# TemperatureMonitor-NTC.net
KiCad netlist of a schematic drawn in EAGLE
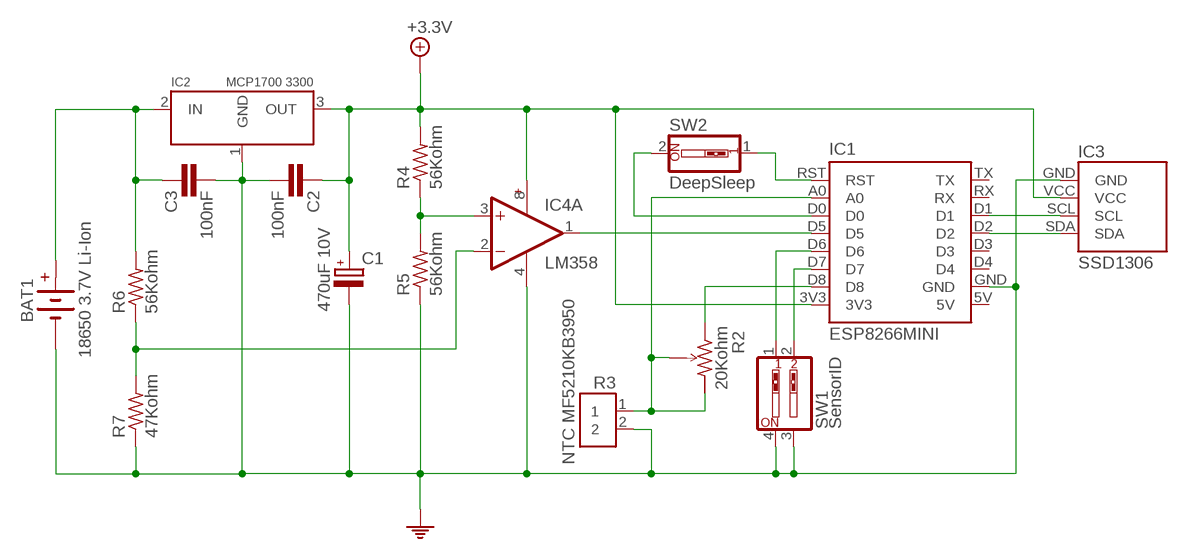
[diagram p0: schematic, sheet 1]

(export (version "E")
  (design (tool "Eeschema 10.0.6"))
  (components
    (comp (ref "BAT1")
      (value "18650 3.7V Li-Ion")
      (footprint "eagle-import:SIL2")
      (libsource (lib "eagle-import") (part "BATTERYSIL2"))
    )
    (comp (ref "C1")
      (value "470uF 10V")
      (footprint "eagle-import:CAPACITOR-5MM")
      (libsource (lib "eagle-import") (part "CAPACITOR_EL5MM"))
    )
    (comp (ref "C2")
      (value "100nF")
      (footprint "eagle-import:CAPACITOR-5MM")
      (libsource (lib "eagle-import") (part "CAPACITOR5MM"))
    )
    (comp (ref "C3")
      (value "100nF")
      (footprint "eagle-import:CAPACITOR-5MM")
      (libsource (lib "eagle-import") (part "CAPACITOR5MM"))
    )
    (comp (ref "IC1")
      (value "ESP8266MINI")
      (footprint "eagle-import:ESP8266MINI")
      (libsource (lib "eagle-import") (part "ESP8266MINI"))
    )
    (comp (ref "IC2")
      (value "MCP1700 3300")
      (footprint "eagle-import:TO92")
      (libsource (lib "eagle-import") (part "MCP1700"))
    )
    (comp (ref "IC3")
      (value "SSD1306")
      (footprint "eagle-import:SSD1306")
      (libsource (lib "eagle-import") (part "SSD1306"))
    )
    (comp (ref "IC4")
      (value "LM358")
      (footprint "eagle-import:DIL8")
      (fields (field (name "SPICEPREFIX") "J"))
      (libsource (lib "eagle-import") (part "LM358"))
    )
    (comp (ref "R2")
      (value "20Kohm")
      (footprint "eagle-import:TRIMMER-A")
      (libsource (lib "eagle-import") (part "TRIMMERA"))
    )
    (comp (ref "R3")
      (value "NTC MF5210KB3950")
      (footprint "eagle-import:JST2")
      (libsource (lib "eagle-import") (part "SIL2JST2"))
    )
    (comp (ref "R4")
      (value "56Kohm")
      (footprint "eagle-import:RESISTOR-0.25W")
      (libsource (lib "eagle-import") (part "RESISTOR0.25W"))
    )
    (comp (ref "R5")
      (value "56Kohm")
      (footprint "eagle-import:RESISTOR-0.25W")
      (libsource (lib "eagle-import") (part "RESISTOR0.25W"))
    )
    (comp (ref "R6")
      (value "56Kohm")
      (footprint "eagle-import:RESISTOR-0.25W")
      (libsource (lib "eagle-import") (part "RESISTOR0.25W"))
    )
    (comp (ref "R7")
      (value "47Kohm")
      (footprint "eagle-import:RESISTOR-0.25W")
      (libsource (lib "eagle-import") (part "RESISTOR0.25W"))
    )
    (comp (ref "SW1")
      (value "SensorID")
      (footprint "eagle-import:DIL4")
      (libsource (lib "eagle-import") (part "DIP-SWITCH-2"))
    )
    (comp (ref "SW2")
      (value "DeepSleep")
      (footprint "eagle-import:DIL2")
      (libsource (lib "eagle-import") (part "DIP-SWITCH-1"))
    )
  )
  (nets
    (net (code "1") (name "+3.3V") (class "Default")
      (node (ref "C1") (pin "1") (pinfunction "1_1") (pintype "passive"))
      (node (ref "C2") (pin "1") (pinfunction "1_1") (pintype "passive"))
      (node (ref "IC1") (pin "3V3") (pinfunction "3V3_3V3") (pintype "power_in"))
      (node (ref "IC2") (pin "3") (pinfunction "OUT_3") (pintype "output"))
      (node (ref "IC3") (pin "VCC") (pinfunction "VCC_VCC") (pintype "power_in"))
      (node (ref "IC4") (pin "8") (pinfunction "V+_8") (pintype "power_in"))
      (node (ref "R4") (pin "2") (pinfunction "2_2") (pintype "passive"))
    )
    (net (code "2") (name "/5V") (class "Default")
      (node (ref "IC1") (pin "5V") (pinfunction "5V_5V") (pintype "power_in"))
    )
    (net (code "3") (name "GND") (class "Default")
      (node (ref "BAT1") (pin "2") (pinfunction "-_2") (pintype "passive"))
      (node (ref "C1") (pin "2") (pinfunction "2_2") (pintype "passive"))
      (node (ref "C2") (pin "2") (pinfunction "2_2") (pintype "passive"))
      (node (ref "C3") (pin "1") (pinfunction "1_1") (pintype "passive"))
      (node (ref "IC1") (pin "GND") (pinfunction "GND_GND") (pintype "power_in"))
      (node (ref "IC2") (pin "1") (pinfunction "GND_1") (pintype "power_in"))
      (node (ref "IC3") (pin "GND") (pinfunction "GND_GND") (pintype "power_in"))
      (node (ref "IC4") (pin "4") (pinfunction "V-_4") (pintype "power_in"))
      (node (ref "R3") (pin "2") (pinfunction "2_2") (pintype "bidirectional"))
      (node (ref "R5") (pin "1") (pinfunction "1_1") (pintype "passive"))
      (node (ref "R7") (pin "1") (pinfunction "1_1") (pintype "passive"))
      (node (ref "SW1") (pin "3") (pinfunction "3_3") (pintype "passive"))
      (node (ref "SW1") (pin "4") (pinfunction "4_4") (pintype "passive"))
    )
    (net (code "4") (name "Net-(BAT1-+)") (class "Default")
      (node (ref "BAT1") (pin "1") (pinfunction "+_1") (pintype "passive"))
      (node (ref "C3") (pin "2") (pinfunction "2_2") (pintype "passive"))
      (node (ref "IC2") (pin "2") (pinfunction "IN_2") (pintype "input"))
      (node (ref "R6") (pin "2") (pinfunction "2_2") (pintype "passive"))
    )
    (net (code "5") (name "Net-(IC1-PadA0)") (class "Default")
      (node (ref "IC1") (pin "A0") (pinfunction "A0_A0") (pintype "bidirectional"))
      (node (ref "R2") (pin "B") (pinfunction "B_B") (pintype "passive"))
      (node (ref "R2") (pin "C") (pinfunction "C_C") (pintype "passive"))
      (node (ref "R3") (pin "1") (pinfunction "1_1") (pintype "bidirectional"))
    )
    (net (code "6") (name "Net-(IC1-PadD0)") (class "Default")
      (node (ref "IC1") (pin "D0") (pinfunction "D0_D0") (pintype "bidirectional"))
      (node (ref "SW2") (pin "2") (pinfunction "2_2") (pintype "passive"))
    )
    (net (code "7") (name "Net-(IC1-PadD1)") (class "Default")
      (node (ref "IC1") (pin "D1") (pinfunction "D1_D1") (pintype "bidirectional"))
      (node (ref "IC3") (pin "SCL") (pinfunction "SCL_SCL") (pintype "bidirectional"))
    )
    (net (code "8") (name "Net-(IC1-PadD2)") (class "Default")
      (node (ref "IC1") (pin "D2") (pinfunction "D2_D2") (pintype "bidirectional"))
      (node (ref "IC3") (pin "SDA") (pinfunction "SDA_SDA") (pintype "bidirectional"))
    )
    (net (code "9") (name "Net-(IC1-PadD6)") (class "Default")
      (node (ref "IC1") (pin "D6") (pinfunction "D6_D6") (pintype "bidirectional"))
      (node (ref "SW1") (pin "1") (pinfunction "1_1") (pintype "passive"))
    )
    (net (code "10") (name "Net-(IC1-PadD7)") (class "Default")
      (node (ref "IC1") (pin "D7") (pinfunction "D7_D7") (pintype "bidirectional"))
      (node (ref "SW1") (pin "2") (pinfunction "2_2") (pintype "passive"))
    )
    (net (code "11") (name "Net-(IC1-PadD8)") (class "Default")
      (node (ref "IC1") (pin "D8") (pinfunction "D8_D8") (pintype "bidirectional"))
      (node (ref "R2") (pin "A") (pinfunction "A_A") (pintype "passive"))
    )
    (net (code "12") (name "Net-(IC1-PadRST)") (class "Default")
      (node (ref "IC1") (pin "RST") (pinfunction "RST_RST") (pintype "bidirectional"))
      (node (ref "SW2") (pin "1") (pinfunction "1_1") (pintype "passive"))
    )
    (net (code "13") (name "Net-(IC4A-+IN)") (class "Default")
      (node (ref "IC4") (pin "3") (pinfunction "+IN_3") (pintype "input"))
      (node (ref "R4") (pin "1") (pinfunction "1_1") (pintype "passive"))
      (node (ref "R5") (pin "2") (pinfunction "2_2") (pintype "passive"))
    )
    (net (code "14") (name "Net-(IC4A--IN)") (class "Default")
      (node (ref "IC4") (pin "2") (pinfunction "-IN_2") (pintype "input"))
      (node (ref "R6") (pin "1") (pinfunction "1_1") (pintype "passive"))
      (node (ref "R7") (pin "2") (pinfunction "2_2") (pintype "passive"))
    )
    (net (code "15") (name "Net-(IC4A-OUT)") (class "Default")
      (node (ref "IC1") (pin "D5") (pinfunction "D5_D5") (pintype "bidirectional"))
      (node (ref "IC4") (pin "1") (pinfunction "OUT_1") (pintype "output"))
    )
    (net (code "16") (name "unconnected-(IC1-PadD3)") (class "Default")
      (node (ref "IC1") (pin "D3") (pinfunction "D3_D3") (pintype "bidirectional"))
    )
    (net (code "17") (name "unconnected-(IC1-PadD4)") (class "Default")
      (node (ref "IC1") (pin "D4") (pinfunction "D4_D4") (pintype "bidirectional"))
    )
    (net (code "18") (name "unconnected-(IC1-PadRX)") (class "Default")
      (node (ref "IC1") (pin "RX") (pinfunction "RX_RX") (pintype "input"))
    )
    (net (code "19") (name "unconnected-(IC1-PadTX)") (class "Default")
      (node (ref "IC1") (pin "TX") (pinfunction "TX_TX") (pintype "output"))
    )
  )
)
